# main.net
KiCad netlist of a schematic drawn in EAGLE
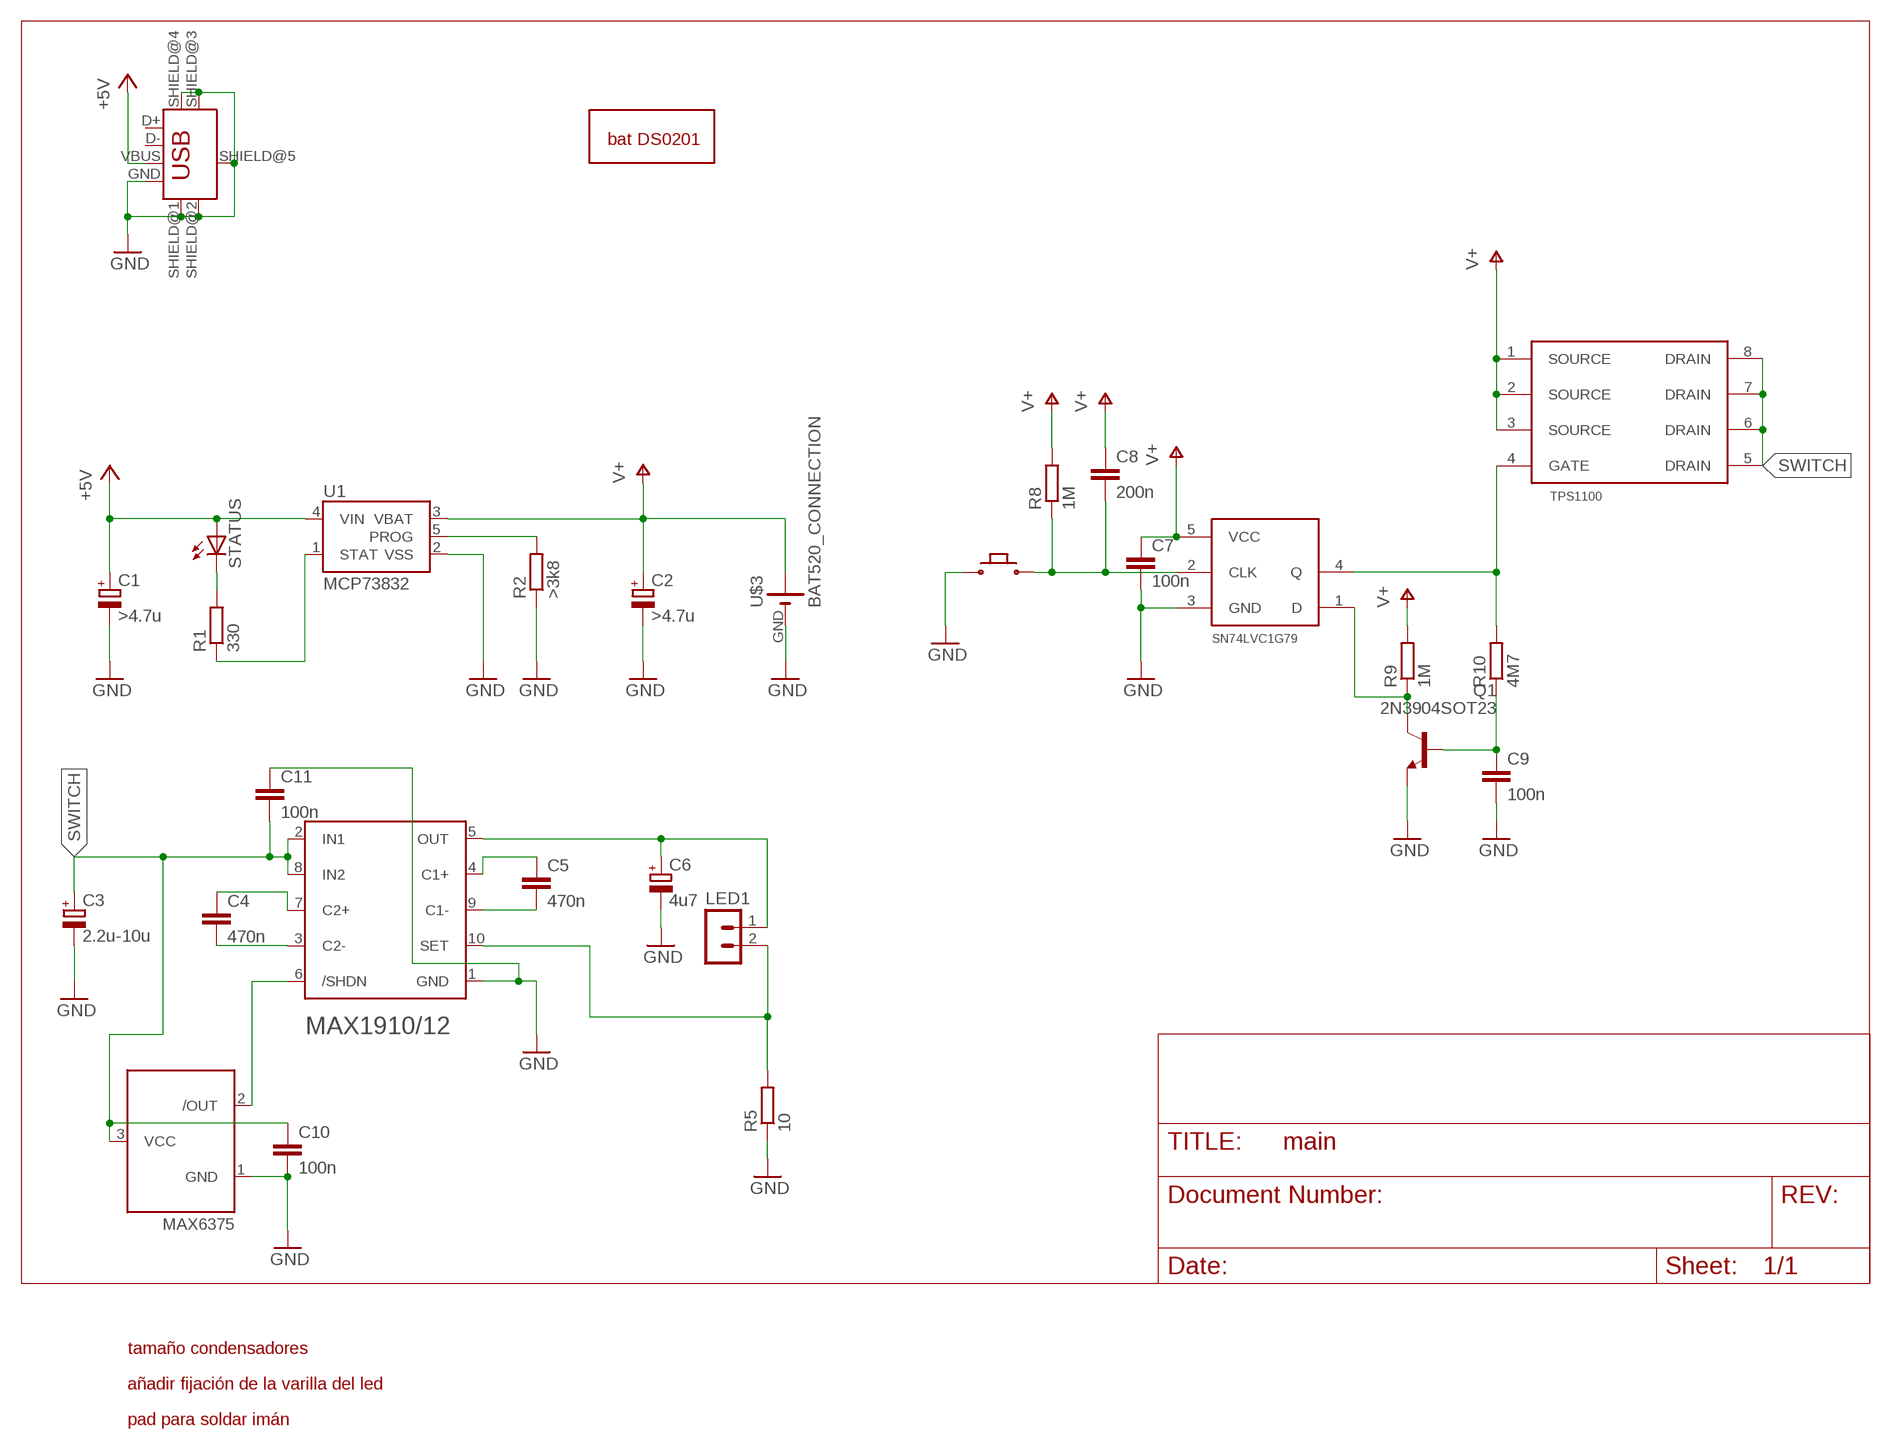
[diagram p0: schematic, sheet 1]

(export (version "E")
  (design (tool "Eeschema 10.0.6"))
  (components
    (comp (ref "C1")
      (value ">4.7u")
      (footprint "eagle-import:SMC_B")
      (libsource (lib "eagle-import") (part "CPOL-EUSMCB"))
    )
    (comp (ref "C2")
      (value ">4.7u")
      (footprint "eagle-import:SMC_B")
      (libsource (lib "eagle-import") (part "CPOL-EUSMCB"))
    )
    (comp (ref "C3")
      (value "2.2u-10u")
      (footprint "eagle-import:SMC_B")
      (libsource (lib "eagle-import") (part "CPOL-EUSMCB"))
    )
    (comp (ref "C4")
      (value "470n")
      (footprint "eagle-import:C1206")
      (libsource (lib "eagle-import") (part "C-EUC1206"))
    )
    (comp (ref "C5")
      (value "470n")
      (footprint "eagle-import:C1206")
      (libsource (lib "eagle-import") (part "C-EUC1206"))
    )
    (comp (ref "C6")
      (value "4u7")
      (footprint "eagle-import:SMC_B")
      (libsource (lib "eagle-import") (part "CPOL-EUSMCB"))
    )
    (comp (ref "C7")
      (value "100n")
      (footprint "eagle-import:C1206")
      (libsource (lib "eagle-import") (part "C-EUC1206"))
    )
    (comp (ref "C8")
      (value "200n")
      (footprint "eagle-import:C1206")
      (libsource (lib "eagle-import") (part "C-EUC1206"))
    )
    (comp (ref "C9")
      (value "100n")
      (footprint "eagle-import:C1206")
      (libsource (lib "eagle-import") (part "C-EUC1206"))
    )
    (comp (ref "C10")
      (value "100n")
      (footprint "eagle-import:C1206")
      (libsource (lib "eagle-import") (part "C-EUC1206"))
    )
    (comp (ref "C11")
      (value "100n")
      (footprint "eagle-import:C1206")
      (libsource (lib "eagle-import") (part "C-EUC1206"))
    )
    (comp (ref "LED1")
      (value "MA02-1")
      (footprint "eagle-import:MA02-1W")
      (libsource (lib "eagle-import") (part "MA02-1"))
    )
    (comp (ref "Q1")
      (value "2N3904SOT23")
      (footprint "eagle-import:SOT23")
      (libsource (lib "eagle-import") (part "2N3904SOT23"))
    )
    (comp (ref "R1")
      (value "330")
      (footprint "eagle-import:R1206")
      (libsource (lib "eagle-import") (part "R-EU_R1206"))
    )
    (comp (ref "R2")
      (value ">3k8")
      (footprint "eagle-import:R1206")
      (libsource (lib "eagle-import") (part "R-EU_R1206"))
    )
    (comp (ref "R5")
      (value "10")
      (footprint "eagle-import:R1206")
      (libsource (lib "eagle-import") (part "R-EU_R1206"))
    )
    (comp (ref "R8")
      (value "1M")
      (footprint "eagle-import:R0805")
      (libsource (lib "eagle-import") (part "R-EU_R0805"))
    )
    (comp (ref "R9")
      (value "1M")
      (footprint "eagle-import:R0805")
      (libsource (lib "eagle-import") (part "R-EU_R0805"))
    )
    (comp (ref "R10")
      (value "4M7")
      (footprint "eagle-import:R1206")
      (libsource (lib "eagle-import") (part "R-EU_R1206"))
    )
    (comp (ref "STATUS")
      (value "LEDCHIPLED_1206")
      (footprint "eagle-import:CHIPLED_1206")
      (libsource (lib "eagle-import") (part "LEDCHIPLED_1206"))
    )
    (comp (ref "U$1")
      (value "MAX1910/12")
      (footprint "eagle-import:UMAX_USOP_10L")
      (libsource (lib "eagle-import") (part "MAX1910/12"))
    )
    (comp (ref "U$2")
      (value "MAX6375")
      (footprint "eagle-import:SC70-3-W")
      (libsource (lib "eagle-import") (part "MAX6375"))
    )
    (comp (ref "U$3")
      (value "BAT520_CONNECTION")
      (footprint "eagle-import:BAT520_CONN_SMD")
      (libsource (lib "eagle-import") (part "BAT520_CONNECTION"))
    )
    (comp (ref "U$4")
      (value "BAT_DS0201_PACKAGE")
      (footprint "eagle-import:BAT_DS0201")
      (libsource (lib "eagle-import") (part "BAT_DS0201_PACKAGE"))
    )
    (comp (ref "U$5")
      (value "MICROUSB_B")
      (footprint "eagle-import:USB-MICROB")
      (libsource (lib "eagle-import") (part "MICROUSB_B"))
    )
    (comp (ref "U$6")
      (value "MICROBUTTON_0072")
      (footprint "eagle-import:MICROBUTTON")
      (libsource (lib "eagle-import") (part "MICROBUTTON_0072"))
    )
    (comp (ref "U$7")
      (value "SN74LVC1G79")
      (footprint "eagle-import:SOT23-5")
      (libsource (lib "eagle-import") (part "SN74LVC1G79"))
    )
    (comp (ref "U$8")
      (value "TPS1100")
      (footprint "eagle-import:SO08")
      (libsource (lib "eagle-import") (part "TPS1100"))
    )
    (comp (ref "U1")
      (value "MCP73832")
      (footprint "eagle-import:SOT23-5")
      (libsource (lib "eagle-import") (part "MCP73832"))
    )
  )
  (nets
    (net (code "1") (name "+5V") (class "Default")
      (node (ref "C1") (pin "+") (pinfunction "+_+") (pintype "passive"))
      (node (ref "STATUS") (pin "A") (pinfunction "A_A") (pintype "passive"))
      (node (ref "U$5") (pin "VBUS") (pinfunction "VBUS_VBUS") (pintype "bidirectional"))
      (node (ref "U1") (pin "4") (pinfunction "VIN_4") (pintype "power_in"))
    )
    (net (code "2") (name "GND") (class "Default")
      (node (ref "C1") (pin "-") (pinfunction "-_-") (pintype "passive"))
      (node (ref "C10") (pin "2") (pinfunction "2_2") (pintype "passive"))
      (node (ref "C11") (pin "1") (pinfunction "1_1") (pintype "passive"))
      (node (ref "C2") (pin "-") (pinfunction "-_-") (pintype "passive"))
      (node (ref "C3") (pin "-") (pinfunction "-_-") (pintype "passive"))
      (node (ref "C6") (pin "-") (pinfunction "-_-") (pintype "passive"))
      (node (ref "C7") (pin "2") (pinfunction "2_2") (pintype "passive"))
      (node (ref "C9") (pin "2") (pinfunction "2_2") (pintype "passive"))
      (node (ref "Q1") (pin "2") (pinfunction "E_2") (pintype "passive"))
      (node (ref "R2") (pin "1") (pinfunction "1_1") (pintype "passive"))
      (node (ref "R5") (pin "1") (pinfunction "1_1") (pintype "passive"))
      (node (ref "U$1") (pin "1") (pinfunction "GND_1") (pintype "power_in"))
      (node (ref "U$2") (pin "1") (pinfunction "GND_1") (pintype "power_in"))
      (node (ref "U$3") (pin "GND") (pinfunction "-_GND") (pintype "passive"))
      (node (ref "U$5") (pin "GND") (pinfunction "GND_GND") (pintype "bidirectional"))
      (node (ref "U$5") (pin "SHIELD@1") (pinfunction "SHIELD_SHIELD@1") (pintype "bidirectional"))
      (node (ref "U$5") (pin "SHIELD@2") (pinfunction "SHIELD_SHIELD@2") (pintype "bidirectional"))
      (node (ref "U$5") (pin "SHIELD@3") (pinfunction "SHIELD_SHIELD@3") (pintype "bidirectional"))
      (node (ref "U$5") (pin "SHIELD@4") (pinfunction "SHIELD_SHIELD@4") (pintype "bidirectional"))
      (node (ref "U$5") (pin "SHIELD@5") (pinfunction "SHIELD_SHIELD@5") (pintype "bidirectional"))
      (node (ref "U$6") (pin "P$2") (pinfunction "P$2_P$2") (pintype "bidirectional"))
      (node (ref "U$7") (pin "3") (pinfunction "GND_3") (pintype "bidirectional"))
      (node (ref "U1") (pin "2") (pinfunction "VSS_2") (pintype "power_in"))
    )
    (net (code "3") (name "Net-(Q1-B)") (class "Default")
      (node (ref "C9") (pin "1") (pinfunction "1_1") (pintype "passive"))
      (node (ref "Q1") (pin "1") (pinfunction "B_1") (pintype "passive"))
      (node (ref "R10") (pin "1") (pinfunction "1_1") (pintype "passive"))
    )
    (net (code "4") (name "Net-(Q1-C)") (class "Default")
      (node (ref "Q1") (pin "3") (pinfunction "C_3") (pintype "passive"))
      (node (ref "R9") (pin "1") (pinfunction "1_1") (pintype "passive"))
      (node (ref "U$7") (pin "1") (pinfunction "D_1") (pintype "bidirectional"))
    )
    (net (code "5") (name "Net-(R1-Pad2)") (class "Default")
      (node (ref "R1") (pin "2") (pinfunction "2_2") (pintype "passive"))
      (node (ref "STATUS") (pin "C") (pinfunction "C_C") (pintype "passive"))
    )
    (net (code "6") (name "Net-(U$1-C1+)") (class "Default")
      (node (ref "C5") (pin "1") (pinfunction "1_1") (pintype "passive"))
      (node (ref "U$1") (pin "4") (pinfunction "C1+_4") (pintype "bidirectional"))
    )
    (net (code "7") (name "Net-(U$1-C1-)") (class "Default")
      (node (ref "C5") (pin "2") (pinfunction "2_2") (pintype "passive"))
      (node (ref "U$1") (pin "9") (pinfunction "C1-_9") (pintype "bidirectional"))
    )
    (net (code "8") (name "Net-(U$1-C2+)") (class "Default")
      (node (ref "C4") (pin "1") (pinfunction "1_1") (pintype "passive"))
      (node (ref "U$1") (pin "7") (pinfunction "C2+_7") (pintype "bidirectional"))
    )
    (net (code "9") (name "Net-(U$1-C2-)") (class "Default")
      (node (ref "C4") (pin "2") (pinfunction "2_2") (pintype "passive"))
      (node (ref "U$1") (pin "3") (pinfunction "C2-_3") (pintype "bidirectional"))
    )
    (net (code "10") (name "Net-(U$1-OUT)") (class "Default")
      (node (ref "C6") (pin "+") (pinfunction "+_+") (pintype "passive"))
      (node (ref "LED1") (pin "1") (pinfunction "1_1") (pintype "passive"))
      (node (ref "U$1") (pin "5") (pinfunction "OUT_5") (pintype "output"))
    )
    (net (code "11") (name "Net-(U$1-SET)") (class "Default")
      (node (ref "LED1") (pin "2") (pinfunction "2_2") (pintype "passive"))
      (node (ref "R5") (pin "2") (pinfunction "2_2") (pintype "passive"))
      (node (ref "U$1") (pin "10") (pinfunction "SET_10") (pintype "input"))
    )
    (net (code "12") (name "Net-(U$1-{slash}SHDN)") (class "Default")
      (node (ref "U$1") (pin "6") (pinfunction "/SHDN_6") (pintype "bidirectional"))
      (node (ref "U$2") (pin "2") (pinfunction "/OUT_2") (pintype "output"))
    )
    (net (code "13") (name "Net-(U$7-CLK)") (class "Default")
      (node (ref "C8") (pin "2") (pinfunction "2_2") (pintype "passive"))
      (node (ref "R8") (pin "1") (pinfunction "1_1") (pintype "passive"))
      (node (ref "U$6") (pin "P$1") (pinfunction "P$1_P$1") (pintype "bidirectional"))
      (node (ref "U$7") (pin "2") (pinfunction "CLK_2") (pintype "bidirectional"))
    )
    (net (code "14") (name "Net-(U$7-Q)") (class "Default")
      (node (ref "R10") (pin "2") (pinfunction "2_2") (pintype "passive"))
      (node (ref "U$7") (pin "4") (pinfunction "Q_4") (pintype "bidirectional"))
      (node (ref "U$8") (pin "4") (pinfunction "GATE_4") (pintype "bidirectional"))
    )
    (net (code "15") (name "Net-(U1-PROG)") (class "Default")
      (node (ref "R2") (pin "2") (pinfunction "2_2") (pintype "passive"))
      (node (ref "U1") (pin "5") (pinfunction "PROG_5") (pintype "input"))
    )
    (net (code "16") (name "Net-(U1-STAT)") (class "Default")
      (node (ref "R1") (pin "1") (pinfunction "1_1") (pintype "passive"))
      (node (ref "U1") (pin "1") (pinfunction "STAT_1") (pintype "output"))
    )
    (net (code "17") (name "SWITCH") (class "Default")
      (node (ref "C10") (pin "1") (pinfunction "1_1") (pintype "passive"))
      (node (ref "C11") (pin "2") (pinfunction "2_2") (pintype "passive"))
      (node (ref "C3") (pin "+") (pinfunction "+_+") (pintype "passive"))
      (node (ref "U$1") (pin "2") (pinfunction "IN1_2") (pintype "power_in"))
      (node (ref "U$1") (pin "8") (pinfunction "IN2_8") (pintype "power_in"))
      (node (ref "U$2") (pin "3") (pinfunction "VCC_3") (pintype "power_in"))
      (node (ref "U$8") (pin "5") (pinfunction "DRAIN_5") (pintype "bidirectional"))
      (node (ref "U$8") (pin "6") (pinfunction "DRAIN_6") (pintype "bidirectional"))
      (node (ref "U$8") (pin "7") (pinfunction "DRAIN_7") (pintype "bidirectional"))
      (node (ref "U$8") (pin "8") (pinfunction "DRAIN_8") (pintype "bidirectional"))
    )
    (net (code "18") (name "V+") (class "Default")
      (node (ref "C2") (pin "+") (pinfunction "+_+") (pintype "passive"))
      (node (ref "C7") (pin "1") (pinfunction "1_1") (pintype "passive"))
      (node (ref "C8") (pin "1") (pinfunction "1_1") (pintype "passive"))
      (node (ref "R8") (pin "2") (pinfunction "2_2") (pintype "passive"))
      (node (ref "R9") (pin "2") (pinfunction "2_2") (pintype "passive"))
      (node (ref "U$3") (pin "VCC") (pinfunction "+_VCC") (pintype "passive"))
      (node (ref "U$7") (pin "5") (pinfunction "VCC_5") (pintype "bidirectional"))
      (node (ref "U$8") (pin "1") (pinfunction "SOURCE_1") (pintype "bidirectional"))
      (node (ref "U$8") (pin "2") (pinfunction "SOURCE_2") (pintype "bidirectional"))
      (node (ref "U$8") (pin "3") (pinfunction "SOURCE_3") (pintype "bidirectional"))
      (node (ref "U1") (pin "3") (pinfunction "VBAT_3") (pintype "power_in"))
    )
    (net (code "19") (name "unconnected-(U$5-PadD+)") (class "Default")
      (node (ref "U$5") (pin "D+") (pinfunction "D+_D+") (pintype "bidirectional"))
    )
    (net (code "20") (name "unconnected-(U$5-PadD-)") (class "Default")
      (node (ref "U$5") (pin "D-") (pinfunction "D-_D-") (pintype "bidirectional"))
    )
  )
)
